# STM8S003F3P6_RF433_315_LEARN_CODE_V1_0.net
KiCad netlist of a schematic drawn in Altium Designer
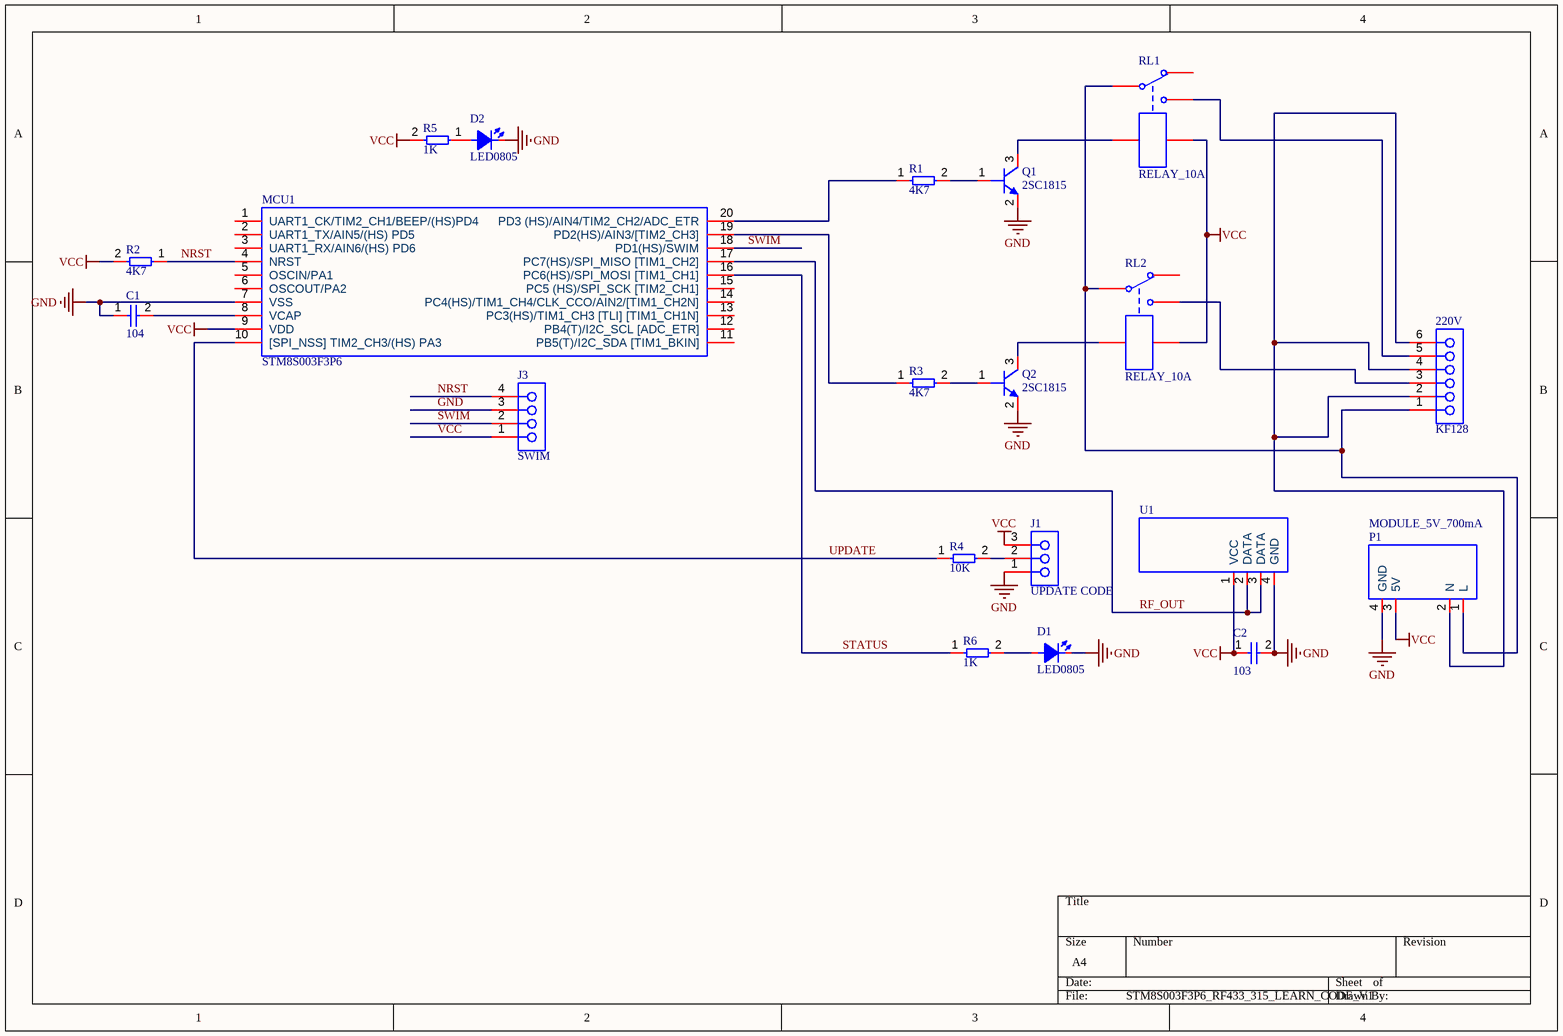
[diagram p0: STM8S003F3P6_RF433_315_LEARN_CODE_V1_0.SchDoc]

(export (version "E")
  (design (tool "Eeschema 10.0.6"))
  (components
    (comp (ref "220V")
      (value "KF128")
      (footprint "HEADER_KF128_6_5.08MM")
      (libsource (lib "Lib31082020") (part "HEADER_KF128_6_5.08MM"))
    )
    (comp (ref "C1") (value "104") (footprint "C0805") (libsource (lib "Lib31082020") (part "C0805")))
    (comp (ref "C2") (value "103") (footprint "C0805") (libsource (lib "Lib31082020") (part "C0805")))
    (comp (ref "D1")
      (value "LED0805")
      (footprint "L0805RED")
      (libsource (lib "Lib31082020") (part "LED0805"))
    )
    (comp (ref "D2")
      (value "LED0805")
      (footprint "L0805RED")
      (libsource (lib "Lib31082020") (part "LED0805"))
    )
    (comp (ref "J1")
      (value "UPDATE CODE")
      (footprint "Header 3x1 TH Pitch 2.54mm")
      (libsource (lib "Lib31082020") (part "Header 3x1 TH Pitch 2.54mm"))
    )
    (comp (ref "J3")
      (value "SWIM")
      (footprint "Header 4x1 TH Pitch 2.54mm")
      (libsource (lib "Lib31082020") (part "Header 4x1 TH Pitch 2.54mm"))
    )
    (comp (ref "MCU1")
      (value "STM8S003F3P6")
      (footprint "TSSOP20_0.65_4.4")
      (libsource (lib "Lib31082020") (part "STM8S003F3P6"))
    )
    (comp (ref "P1")
      (value "MODULE_5V_700mA")
      (footprint "MODULE_5V_700mA")
      (libsource (lib "Lib31082020") (part "MODULE_5V_700mA"))
    )
    (comp (ref "Q1")
      (value "2SC1815")
      (footprint "SOT23-3")
      (libsource (lib "Lib31082020") (part "2SC1815 (SOT-23)"))
    )
    (comp (ref "Q2")
      (value "2SC1815")
      (footprint "SOT23-3")
      (libsource (lib "Lib31082020") (part "2SC1815 (SOT-23)"))
    )
    (comp (ref "R1") (value "4K7") (footprint "R0805") (libsource (lib "Lib31082020") (part "Resistor SMD")))
    (comp (ref "R2") (value "4K7") (footprint "R0805") (libsource (lib "") (part "Resistor SMD_1")))
    (comp (ref "R3") (value "4K7") (footprint "R0805") (libsource (lib "Lib31082020") (part "Resistor SMD")))
    (comp (ref "R4") (value "10K") (footprint "R0805") (libsource (lib "Lib31082020") (part "Resistor SMD")))
    (comp (ref "R5") (value "1K") (footprint "R0805") (libsource (lib "") (part "Resistor SMD_1")))
    (comp (ref "R6") (value "1K") (footprint "R0805") (libsource (lib "Lib31082020") (part "Resistor SMD")))
    (comp (ref "RL1")
      (value "RELAY_10A")
      (footprint "RELAY_10A_5PIN")
      (libsource (lib "Lib31082020") (part "RELAY_10A"))
    )
    (comp (ref "RL2")
      (value "RELAY_10A")
      (footprint "RELAY_10A_5PIN")
      (libsource (lib "Lib31082020") (part "RELAY_10A"))
    )
    (comp (ref "U1")
      (value "RF433_315_RECEVICE")
      (footprint "RF433_315_RECEVICE")
      (libsource (lib "Lib31082020") (part "RF433_315"))
    )
  )
  (nets
    (net (code "1") (name "/NRST") (class "Default")
      (node (ref "J3") (pin "4") (pinfunction "4_4") (pintype "passive"))
      (node (ref "MCU1") (pin "4") (pinfunction "NRST_4") (pintype "passive"))
      (node (ref "R2") (pin "1") (pinfunction "1_1") (pintype "passive"))
    )
    (net (code "2") (name "/RF_OUT") (class "Default")
      (node (ref "MCU1") (pin "17") (pinfunction "PC7(HS)/SPI_MISO_[TIM1_CH2]_17") (pintype "passive"))
      (node (ref "U1") (pin "2") (pinfunction "DATA_2") (pintype "passive"))
      (node (ref "U1") (pin "3") (pinfunction "DATA_3") (pintype "passive"))
    )
    (net (code "3") (name "/STATUS") (class "Default")
      (node (ref "MCU1") (pin "16") (pinfunction "PC6(HS)/SPI_MOSI_[TIM1_CH1]_16") (pintype "passive"))
      (node (ref "R6") (pin "1") (pinfunction "1_1") (pintype "passive"))
    )
    (net (code "4") (name "/SWIM") (class "Default")
      (node (ref "J3") (pin "2") (pinfunction "2_2") (pintype "passive"))
      (node (ref "MCU1") (pin "18") (pinfunction "PD1(HS)/SWIM_18") (pintype "passive"))
    )
    (net (code "5") (name "/UPDATE") (class "Default")
      (node (ref "MCU1") (pin "10") (pinfunction "[SPI_NSS]_TIM2_CH3/(HS)_PA3_10") (pintype "passive"))
      (node (ref "R4") (pin "1") (pinfunction "1_1") (pintype "passive"))
    )
    (net (code "6") (name "GND") (class "Default")
      (node (ref "C1") (pin "1") (pinfunction "1_1") (pintype "passive"))
      (node (ref "C2") (pin "2") (pinfunction "2_2") (pintype "passive"))
      (node (ref "D1") (pin "2") (pinfunction "K_2") (pintype "passive"))
      (node (ref "D2") (pin "2") (pinfunction "K_2") (pintype "passive"))
      (node (ref "J1") (pin "1") (pinfunction "1_1") (pintype "passive"))
      (node (ref "J3") (pin "3") (pinfunction "3_3") (pintype "passive"))
      (node (ref "MCU1") (pin "7") (pinfunction "VSS_7") (pintype "passive"))
      (node (ref "P1") (pin "4") (pinfunction "GND_4") (pintype "passive"))
      (node (ref "Q1") (pin "2") (pinfunction "E_2") (pintype "passive"))
      (node (ref "Q2") (pin "2") (pinfunction "E_2") (pintype "passive"))
      (node (ref "U1") (pin "4") (pinfunction "GND_4") (pintype "passive"))
    )
    (net (code "7") (name "Net-(220V-Pad3)") (class "Default")
      (node (ref "220V") (pin "3") (pinfunction "3_3") (pintype "passive"))
      (node (ref "RL2") (pin "5") (pinfunction "5_5") (pintype "passive"))
    )
    (net (code "8") (name "Net-(220V-Pad5)") (class "Default")
      (node (ref "220V") (pin "5") (pinfunction "5_5") (pintype "passive"))
      (node (ref "RL1") (pin "5") (pinfunction "5_5") (pintype "passive"))
    )
    (net (code "9") (name "Net-(D1-A)") (class "Default")
      (node (ref "D1") (pin "1") (pinfunction "A_1") (pintype "passive"))
      (node (ref "R6") (pin "2") (pinfunction "2_2") (pintype "passive"))
    )
    (net (code "10") (name "Net-(D2-A)") (class "Default")
      (node (ref "D2") (pin "1") (pinfunction "A_1") (pintype "passive"))
      (node (ref "R5") (pin "1") (pinfunction "1_1") (pintype "passive"))
    )
    (net (code "11") (name "Net-(J1-Pad2)") (class "Default")
      (node (ref "J1") (pin "2") (pinfunction "2_2") (pintype "passive"))
      (node (ref "R4") (pin "2") (pinfunction "2_2") (pintype "passive"))
    )
    (net (code "12") (name "Net-(MCU1-PD2(HS){slash}AIN3{slash}[TIM2_CH3])") (class "Default")
      (node (ref "MCU1") (pin "19") (pinfunction "PD2(HS)/AIN3/[TIM2_CH3]_19") (pintype "passive"))
      (node (ref "R3") (pin "1") (pinfunction "1_1") (pintype "passive"))
    )
    (net (code "13") (name "Net-(MCU1-PD3_(HS){slash}AIN4{slash}TIM2_CH2{slash}ADC_ETR)") (class "Default")
      (node (ref "MCU1") (pin "20") (pinfunction "PD3_(HS)/AIN4/TIM2_CH2/ADC_ETR_20") (pintype "passive"))
      (node (ref "R1") (pin "1") (pinfunction "1_1") (pintype "passive"))
    )
    (net (code "14") (name "Net-(MCU1-VCAP)") (class "Default")
      (node (ref "C1") (pin "2") (pinfunction "2_2") (pintype "passive"))
      (node (ref "MCU1") (pin "8") (pinfunction "VCAP_8") (pintype "passive"))
    )
    (net (code "15") (name "Net-(P1-L)") (class "Default")
      (node (ref "220V") (pin "1") (pinfunction "1_1") (pintype "passive"))
      (node (ref "P1") (pin "1") (pinfunction "L_1") (pintype "passive"))
      (node (ref "RL1") (pin "2") (pinfunction "2_2") (pintype "passive"))
      (node (ref "RL2") (pin "2") (pinfunction "2_2") (pintype "passive"))
    )
    (net (code "16") (name "Net-(P1-N)") (class "Default")
      (node (ref "220V") (pin "2") (pinfunction "2_2") (pintype "passive"))
      (node (ref "220V") (pin "4") (pinfunction "4_4") (pintype "passive"))
      (node (ref "220V") (pin "6") (pinfunction "6_6") (pintype "passive"))
      (node (ref "P1") (pin "2") (pinfunction "N_2") (pintype "passive"))
    )
    (net (code "17") (name "Net-(Q1-B)") (class "Default")
      (node (ref "Q1") (pin "1") (pinfunction "B_1") (pintype "passive"))
      (node (ref "R1") (pin "2") (pinfunction "2_2") (pintype "passive"))
    )
    (net (code "18") (name "Net-(Q1-C)") (class "Default")
      (node (ref "Q1") (pin "3") (pinfunction "C_3") (pintype "passive"))
      (node (ref "RL1") (pin "1") (pinfunction "1_1") (pintype "passive"))
    )
    (net (code "19") (name "Net-(Q2-B)") (class "Default")
      (node (ref "Q2") (pin "1") (pinfunction "B_1") (pintype "passive"))
      (node (ref "R3") (pin "2") (pinfunction "2_2") (pintype "passive"))
    )
    (net (code "20") (name "Net-(Q2-C)") (class "Default")
      (node (ref "Q2") (pin "3") (pinfunction "C_3") (pintype "passive"))
      (node (ref "RL2") (pin "1") (pinfunction "1_1") (pintype "passive"))
    )
    (net (code "21") (name "VCC") (class "Default")
      (node (ref "C2") (pin "1") (pinfunction "1_1") (pintype "passive"))
      (node (ref "J1") (pin "3") (pinfunction "3_3") (pintype "passive"))
      (node (ref "J3") (pin "1") (pinfunction "1_1") (pintype "passive"))
      (node (ref "MCU1") (pin "9") (pinfunction "VDD_9") (pintype "passive"))
      (node (ref "P1") (pin "3") (pinfunction "5V_3") (pintype "passive"))
      (node (ref "R2") (pin "2") (pinfunction "2_2") (pintype "passive"))
      (node (ref "R5") (pin "2") (pinfunction "2_2") (pintype "passive"))
      (node (ref "RL1") (pin "3") (pinfunction "3_3") (pintype "passive"))
      (node (ref "RL2") (pin "3") (pinfunction "3_3") (pintype "passive"))
      (node (ref "U1") (pin "1") (pinfunction "VCC_1") (pintype "passive"))
    )
    (net (code "22") (name "unconnected-(MCU1-OSCIN{slash}PA1-Pad5)") (class "Default")
      (node (ref "MCU1") (pin "5") (pinfunction "OSCIN/PA1_5") (pintype "passive"))
    )
    (net (code "23") (name "unconnected-(MCU1-OSCOUT{slash}PA2-Pad6)") (class "Default")
      (node (ref "MCU1") (pin "6") (pinfunction "OSCOUT/PA2_6") (pintype "passive"))
    )
    (net (code "24") (name "unconnected-(MCU1-PB4(T){slash}I2C_SCL_[ADC_ETR]-Pad12)") (class "Default")
      (node (ref "MCU1") (pin "12") (pinfunction "PB4(T)/I2C_SCL_[ADC_ETR]_12") (pintype "passive"))
    )
    (net (code "25") (name "unconnected-(MCU1-PB5(T){slash}I2C_SDA_[TIM1_BKIN]-Pad11)") (class "Default")
      (node (ref "MCU1") (pin "11") (pinfunction "PB5(T)/I2C_SDA_[TIM1_BKIN]_11") (pintype "passive"))
    )
    (net (code "26") (name "unconnected-(MCU1-PC3(HS){slash}TIM1_CH3_[TLI]_[TIM1_CH1N]-Pad13)") (class "Default")
      (node (ref "MCU1") (pin "13") (pinfunction "PC3(HS)/TIM1_CH3_[TLI]_[TIM1_CH1N]_13") (pintype "passive"))
    )
    (net (code "27") (name "unconnected-(MCU1-PC4(HS){slash}TIM1_CH4{slash}CLK_CCO{slash}AIN2{slash}[TIM1_CH2N]-Pad14)") (class "Default")
      (node (ref "MCU1") (pin "14") (pinfunction "PC4(HS)/TIM1_CH4/CLK_CCO/AIN2/[TIM1_CH2N]_14") (pintype "passive"))
    )
    (net (code "28") (name "unconnected-(MCU1-PC5_(HS){slash}SPI_SCK_[TIM2_CH1]-Pad15)") (class "Default")
      (node (ref "MCU1") (pin "15") (pinfunction "PC5_(HS)/SPI_SCK_[TIM2_CH1]_15") (pintype "passive"))
    )
    (net (code "29") (name "unconnected-(MCU1-UART1_CK{slash}TIM2_CH1{slash}BEEP{slash}(HS)PD4-Pad1)") (class "Default")
      (node (ref "MCU1") (pin "1") (pinfunction "UART1_CK/TIM2_CH1/BEEP/(HS)PD4_1") (pintype "passive"))
    )
    (net (code "30") (name "unconnected-(MCU1-UART1_RX{slash}AIN6{slash}(HS)_PD6-Pad3)") (class "Default")
      (node (ref "MCU1") (pin "3") (pinfunction "UART1_RX/AIN6/(HS)_PD6_3") (pintype "passive"))
    )
    (net (code "31") (name "unconnected-(MCU1-UART1_TX{slash}AIN5{slash}(HS)_PD5-Pad2)") (class "Default")
      (node (ref "MCU1") (pin "2") (pinfunction "UART1_TX/AIN5/(HS)_PD5_2") (pintype "passive"))
    )
    (net (code "32") (name "unconnected-(RL1-Pad4)") (class "Default")
      (node (ref "RL1") (pin "4") (pinfunction "4_4") (pintype "passive"))
    )
    (net (code "33") (name "unconnected-(RL2-Pad4)") (class "Default")
      (node (ref "RL2") (pin "4") (pinfunction "4_4") (pintype "passive"))
    )
  )
)
